# KMO_IO_MV1_0.net
KiCad netlist of a schematic drawn in EAGLE
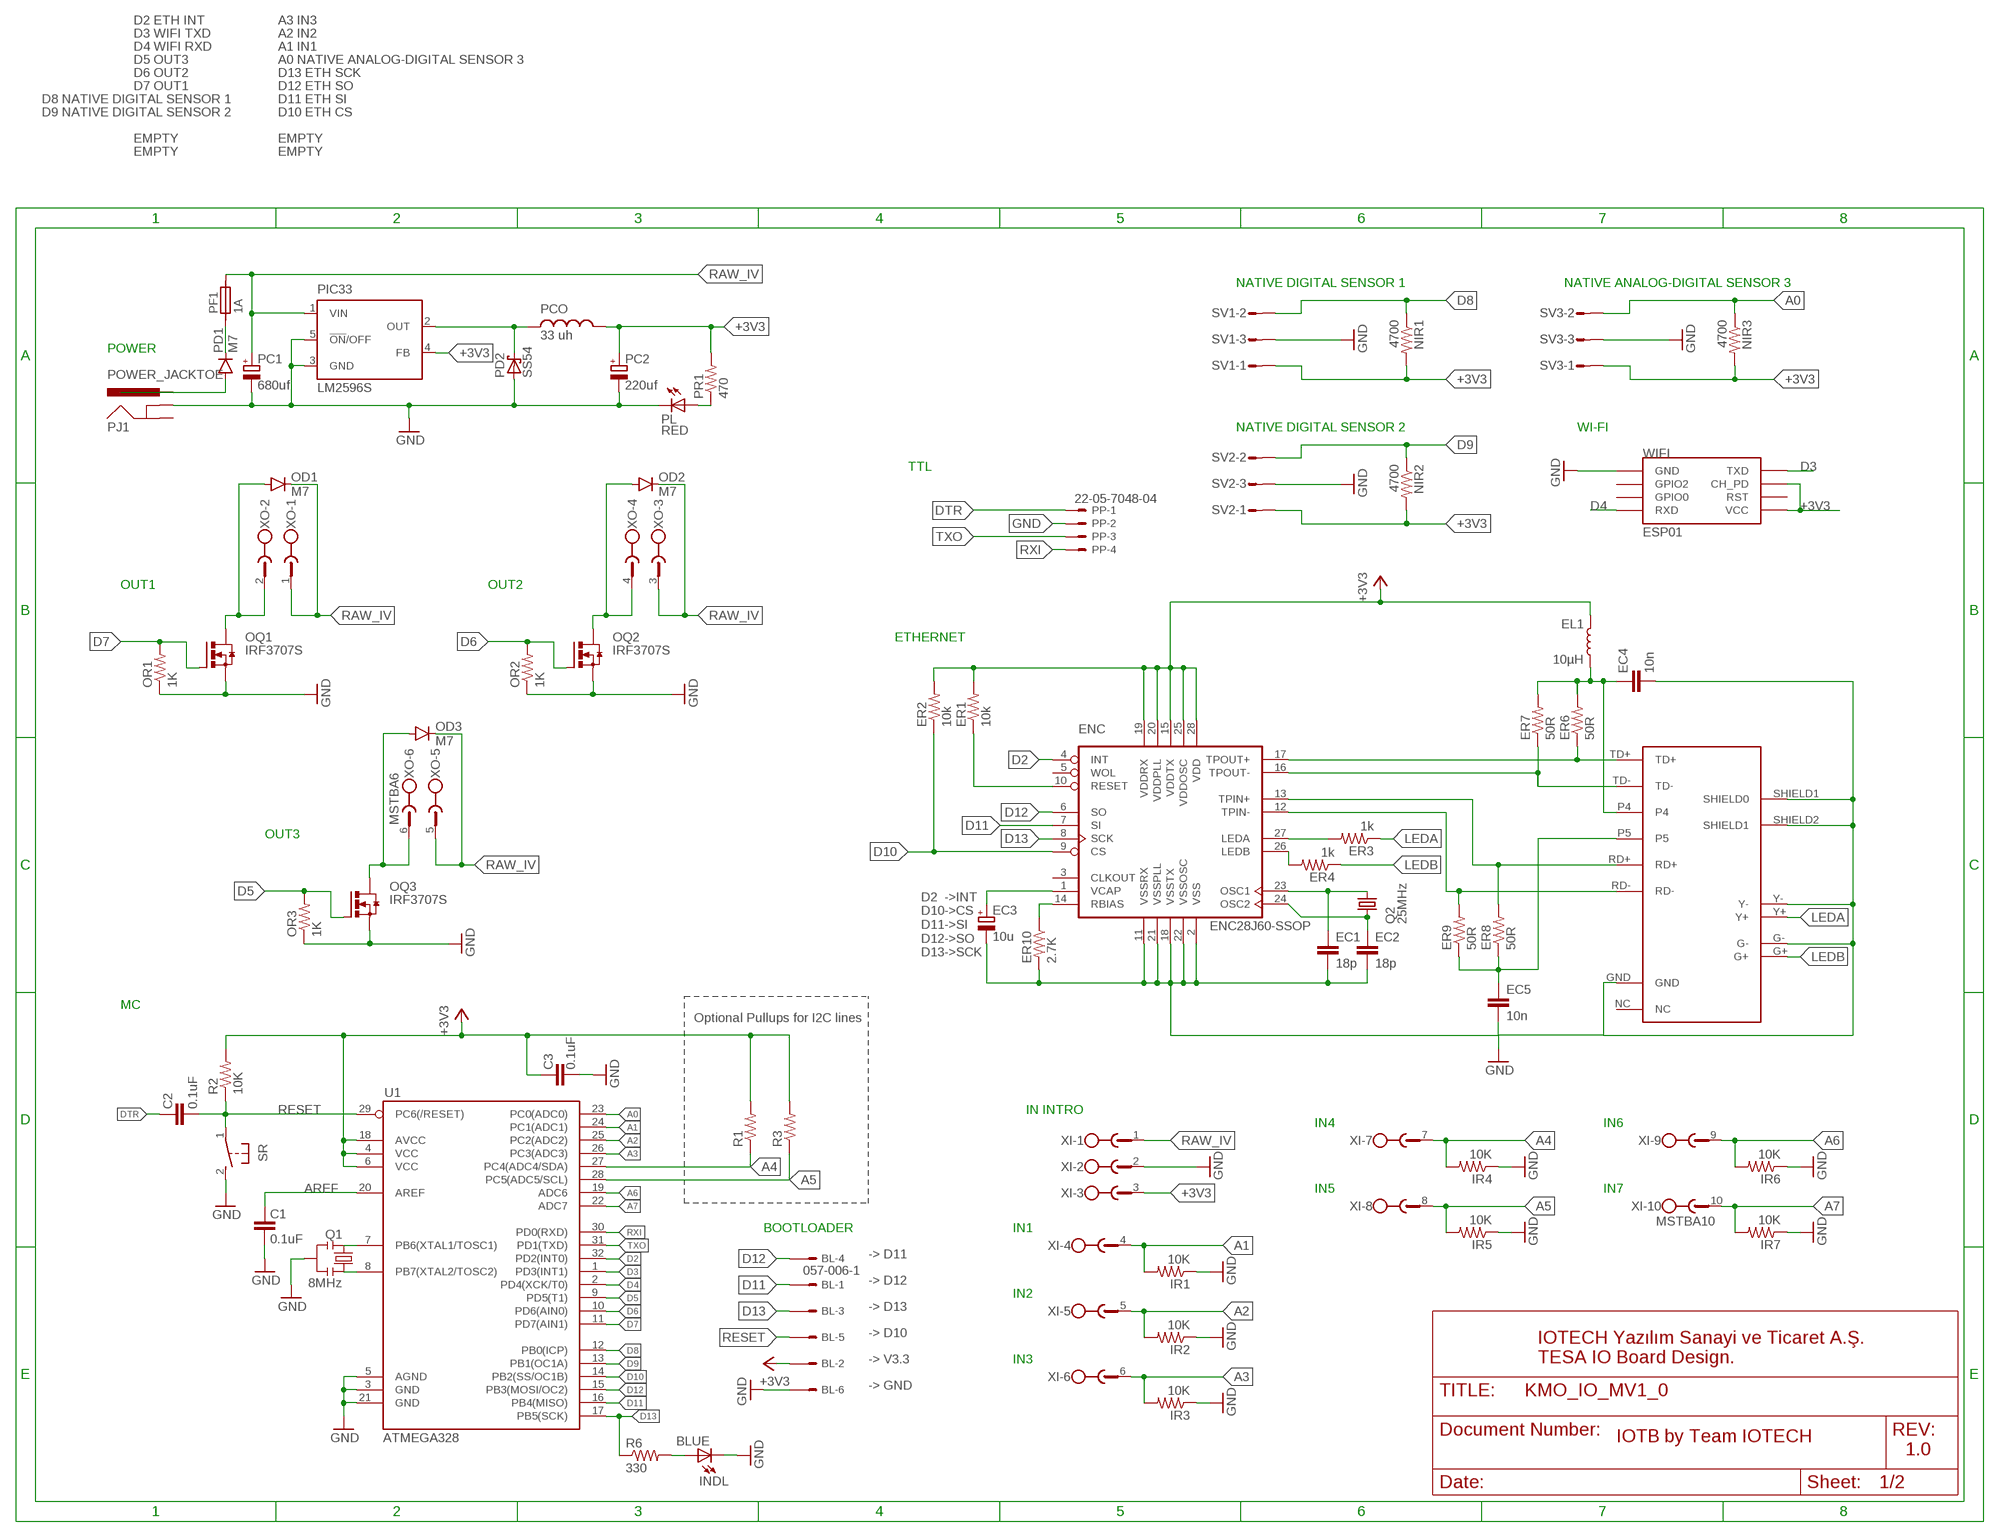
[diagram p0: schematic, sheet 1]
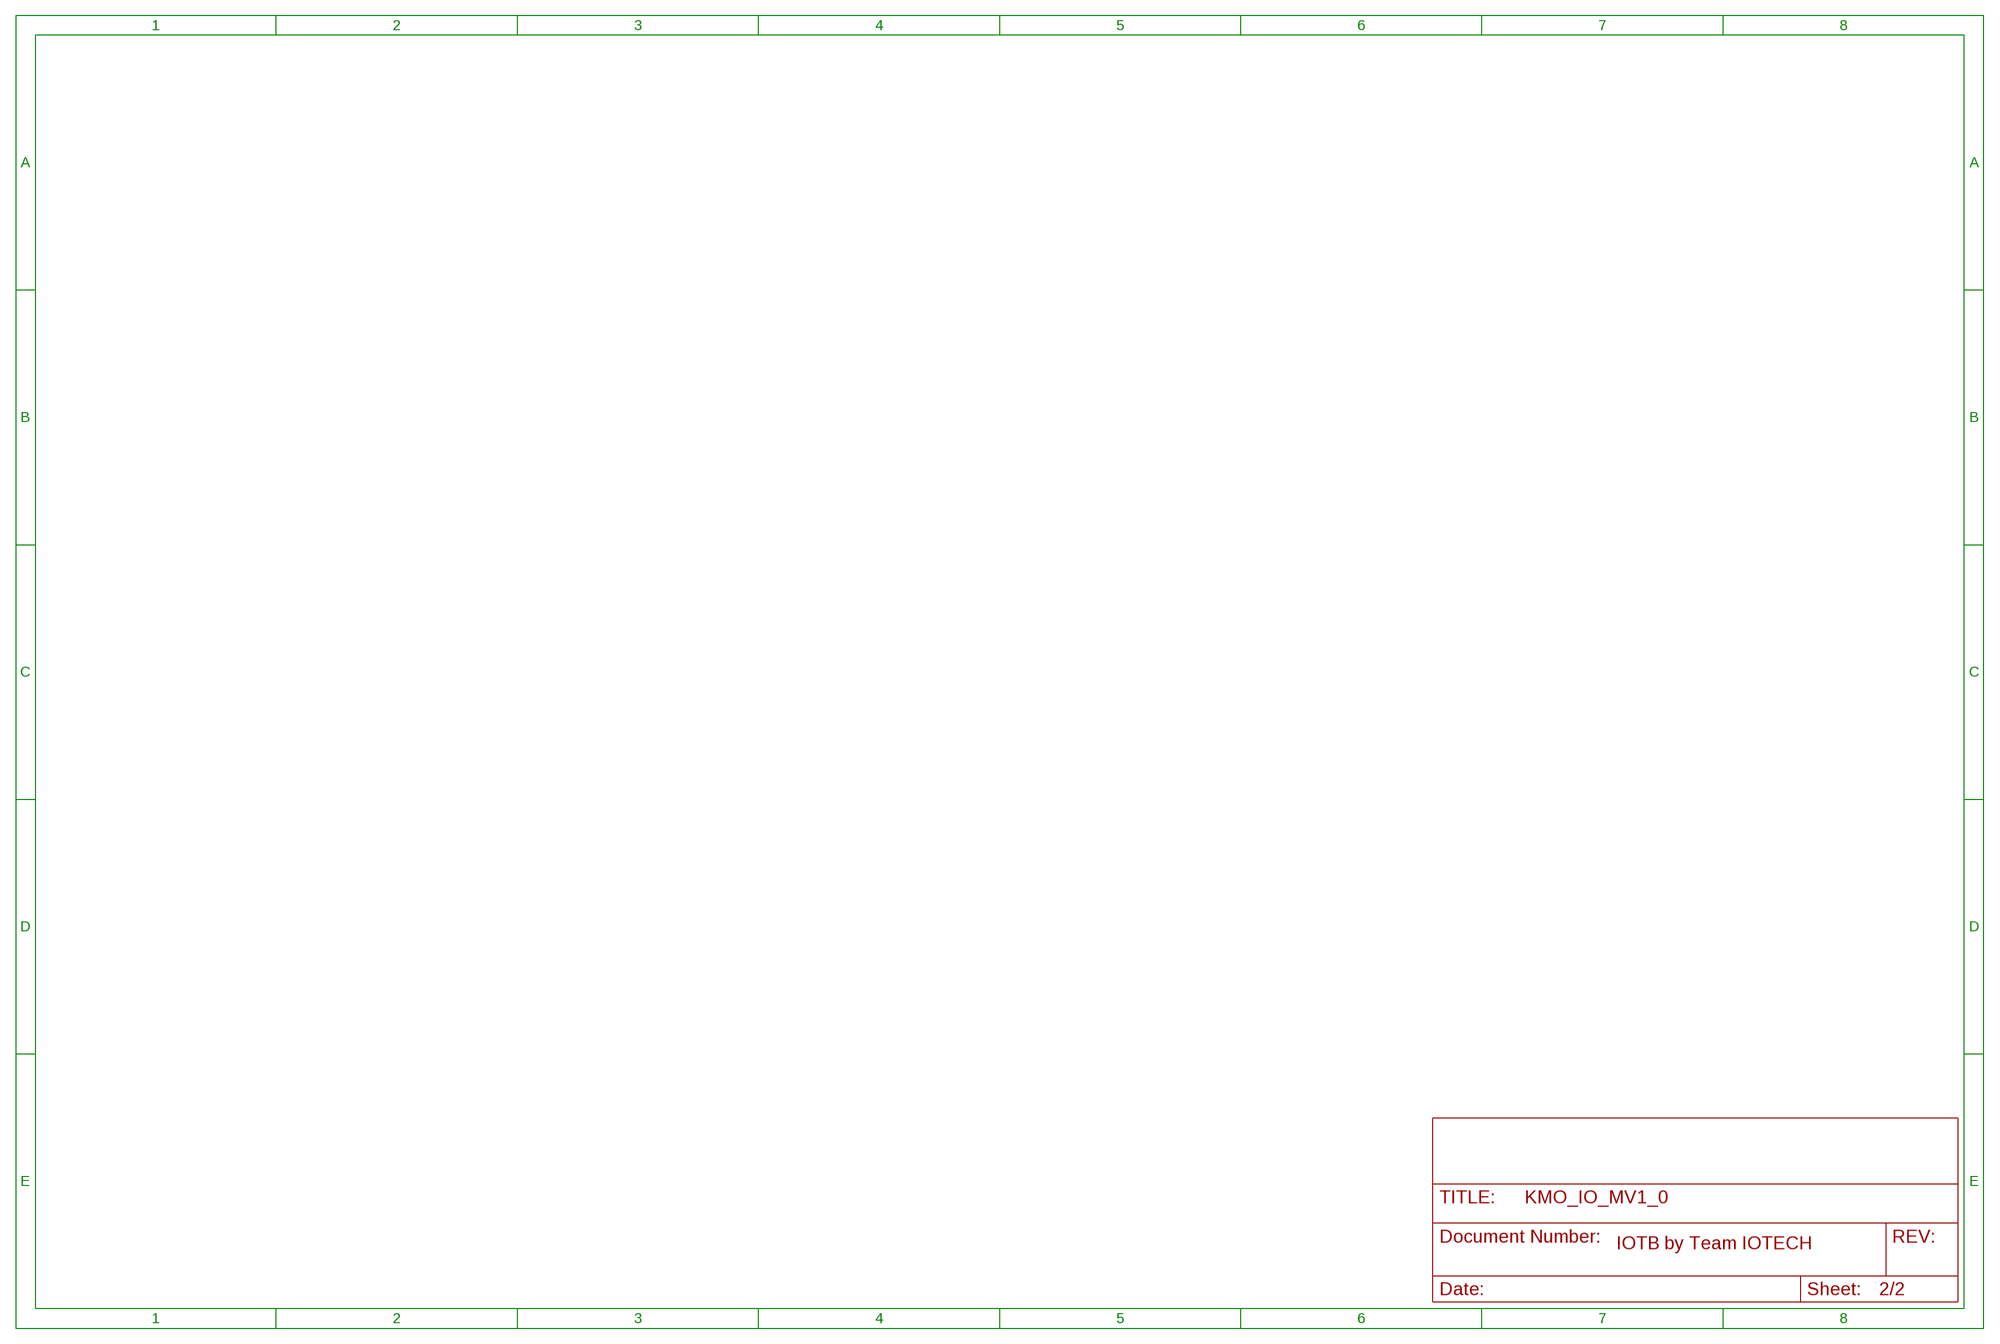
[diagram p1: schematic, sheet 2]

(export (version "E")
  (design (tool "Eeschema 10.0.6"))
  (components
    (comp (ref "BL")
      (value "057-006-1")
      (footprint "eagle-import:057-006-1")
      (libsource (lib "eagle-import") (part "057-006-1"))
    )
    (comp (ref "C1")
      (value "0.1uF")
      (footprint "eagle-import:0805")
      (libsource (lib "eagle-import") (part "CAP0805"))
    )
    (comp (ref "C2")
      (value "0.1uF")
      (footprint "eagle-import:0805")
      (libsource (lib "eagle-import") (part "CAP0805"))
    )
    (comp (ref "C3")
      (value "0.1uF")
      (footprint "eagle-import:0805")
      (libsource (lib "eagle-import") (part "CAP0805"))
    )
    (comp (ref "EC1")
      (value "18p")
      (footprint "eagle-import:0805")
      (libsource (lib "eagle-import") (part "CAP0805"))
    )
    (comp (ref "EC2")
      (value "18p")
      (footprint "eagle-import:0805")
      (libsource (lib "eagle-import") (part "CAP0805"))
    )
    (comp (ref "EC3")
      (value "10u")
      (footprint "eagle-import:CT3216")
      (libsource (lib "eagle-import") (part "CPOL-EUCT3216"))
    )
    (comp (ref "EC4")
      (value "10n")
      (footprint "eagle-import:0805")
      (libsource (lib "eagle-import") (part "CAP0805"))
    )
    (comp (ref "EC5")
      (value "10n")
      (footprint "eagle-import:0805")
      (libsource (lib "eagle-import") (part "CAP0805"))
    )
    (comp (ref "EL1")
      (value "10µH")
      (footprint "eagle-import:0805")
      (libsource (lib "eagle-import") (part "INDUCTOR-0805-3.3UH"))
    )
    (comp (ref "ENC")
      (value "ENC28J60-SSOP")
      (footprint "eagle-import:SSOP28")
      (libsource (lib "eagle-import") (part "ENC28J60-SSOP"))
    )
    (comp (ref "ER1")
      (value "10k")
      (footprint "eagle-import:0805")
      (libsource (lib "eagle-import") (part "RESISTOR0805-RES"))
    )
    (comp (ref "ER2")
      (value "10k")
      (footprint "eagle-import:0805")
      (libsource (lib "eagle-import") (part "RESISTOR0805-RES"))
    )
    (comp (ref "ER3")
      (value "1k")
      (footprint "eagle-import:0805")
      (libsource (lib "eagle-import") (part "RESISTOR0805-RES"))
    )
    (comp (ref "ER4")
      (value "1k")
      (footprint "eagle-import:0805")
      (libsource (lib "eagle-import") (part "RESISTOR0805-RES"))
    )
    (comp (ref "ER6")
      (value "50R")
      (footprint "eagle-import:0805")
      (libsource (lib "eagle-import") (part "RESISTOR0805-RES"))
    )
    (comp (ref "ER7")
      (value "50R")
      (footprint "eagle-import:0805")
      (libsource (lib "eagle-import") (part "RESISTOR0805-RES"))
    )
    (comp (ref "ER8")
      (value "50R")
      (footprint "eagle-import:0805")
      (libsource (lib "eagle-import") (part "RESISTOR0805-RES"))
    )
    (comp (ref "ER9")
      (value "50R")
      (footprint "eagle-import:0805")
      (libsource (lib "eagle-import") (part "RESISTOR0805-RES"))
    )
    (comp (ref "ER10")
      (value "2.7K")
      (footprint "eagle-import:0805")
      (libsource (lib "eagle-import") (part "RESISTOR0805-RES"))
    )
    (comp (ref "INDL")
      (value "BLUE")
      (footprint "eagle-import:CHIP-LED0805")
      (libsource (lib "eagle-import") (part "LEDCHIP-LED0805"))
    )
    (comp (ref "IR1")
      (value "10K")
      (footprint "eagle-import:0805")
      (libsource (lib "eagle-import") (part "RESISTOR0805-RES"))
    )
    (comp (ref "IR2")
      (value "10K")
      (footprint "eagle-import:0805")
      (libsource (lib "eagle-import") (part "RESISTOR0805-RES"))
    )
    (comp (ref "IR3")
      (value "10K")
      (footprint "eagle-import:0805")
      (libsource (lib "eagle-import") (part "RESISTOR0805-RES"))
    )
    (comp (ref "IR4")
      (value "10K")
      (footprint "eagle-import:0805")
      (libsource (lib "eagle-import") (part "RESISTOR0805-RES"))
    )
    (comp (ref "IR5")
      (value "10K")
      (footprint "eagle-import:0805")
      (libsource (lib "eagle-import") (part "RESISTOR0805-RES"))
    )
    (comp (ref "IR6")
      (value "10K")
      (footprint "eagle-import:0805")
      (libsource (lib "eagle-import") (part "RESISTOR0805-RES"))
    )
    (comp (ref "IR7")
      (value "10K")
      (footprint "eagle-import:0805")
      (libsource (lib "eagle-import") (part "RESISTOR0805-RES"))
    )
    (comp (ref "NIR1")
      (value "4700")
      (footprint "eagle-import:0805")
      (libsource (lib "eagle-import") (part "RESISTOR0805-RES"))
    )
    (comp (ref "NIR2")
      (value "4700")
      (footprint "eagle-import:0805")
      (libsource (lib "eagle-import") (part "RESISTOR0805-RES"))
    )
    (comp (ref "NIR3")
      (value "4700")
      (footprint "eagle-import:0805")
      (libsource (lib "eagle-import") (part "RESISTOR0805-RES"))
    )
    (comp (ref "OD1")
      (value "M7")
      (footprint "eagle-import:SMA-DIODE")
      (libsource (lib "eagle-import") (part "DIODESMA"))
    )
    (comp (ref "OD2")
      (value "M7")
      (footprint "eagle-import:SMA-DIODE")
      (libsource (lib "eagle-import") (part "DIODESMA"))
    )
    (comp (ref "OD3")
      (value "M7")
      (footprint "eagle-import:SMA-DIODE")
      (libsource (lib "eagle-import") (part "DIODESMA"))
    )
    (comp (ref "OQ1")
      (value "IRF3707S")
      (footprint "eagle-import:D2PACK")
      (libsource (lib "eagle-import") (part "IRF3704S"))
    )
    (comp (ref "OQ2")
      (value "IRF3707S")
      (footprint "eagle-import:D2PACK")
      (libsource (lib "eagle-import") (part "IRF3704S"))
    )
    (comp (ref "OQ3")
      (value "IRF3707S")
      (footprint "eagle-import:D2PACK")
      (libsource (lib "eagle-import") (part "IRF3704S"))
    )
    (comp (ref "OR1")
      (value "1K")
      (footprint "eagle-import:0805")
      (libsource (lib "eagle-import") (part "RESISTOR0805-RES"))
    )
    (comp (ref "OR2")
      (value "1K")
      (footprint "eagle-import:0805")
      (libsource (lib "eagle-import") (part "RESISTOR0805-RES"))
    )
    (comp (ref "OR3")
      (value "1K")
      (footprint "eagle-import:0805")
      (libsource (lib "eagle-import") (part "RESISTOR0805-RES"))
    )
    (comp (ref "PC1")
      (value "680uf")
      (footprint "eagle-import:140CLH-1010")
      (libsource (lib "eagle-import") (part "CPOL-EU140CLH-1010"))
    )
    (comp (ref "PC2")
      (value "220uf")
      (footprint "eagle-import:140CLH-1010")
      (libsource (lib "eagle-import") (part "CPOL-EU140CLH-1010"))
    )
    (comp (ref "PCO")
      (value "33 uh")
      (footprint "eagle-import:MSS1260")
      (libsource (lib "eagle-import") (part "MSS1260"))
    )
    (comp (ref "PD1")
      (value "M7")
      (footprint "eagle-import:SMA-DIODE")
      (libsource (lib "eagle-import") (part "DIODESMA"))
    )
    (comp (ref "PD2")
      (value "SS54")
      (footprint "eagle-import:SMB")
      (libsource (lib "eagle-import") (part "SCHOTTKY-DIODESMD"))
    )
    (comp (ref "PF1")
      (value "1A")
      (footprint "eagle-import:1820")
      (libsource (lib "eagle-import") (part "SIBA194600"))
    )
    (comp (ref "PIC33")
      (value "LM2596S")
      (footprint "eagle-import:TO263-5")
      (fields (field (name "MF") "NATIONAL SEMICONDUCTOR") (field (name "MPN") "LM2596S-ADJ/NOPB"))
      (libsource (lib "eagle-import") (part "LM2596S"))
    )
    (comp (ref "PJ1")
      (value "POWER_JACKTOE")
      (footprint "eagle-import:POWER_JACK_SMD_OVERPASTE_TOE")
      (libsource (lib "eagle-import") (part "POWER_JACKTOE"))
    )
    (comp (ref "PL")
      (value "RED")
      (footprint "eagle-import:CHIP-LED0805")
      (libsource (lib "eagle-import") (part "LEDCHIP-LED0805"))
    )
    (comp (ref "PP")
      (value "22-05-7048-04")
      (footprint "eagle-import:7395-04")
      (fields (field (name "MF") "MOLEX"))
      (libsource (lib "eagle-import") (part "22-?-0405-7048"))
    )
    (comp (ref "PR1")
      (value "470")
      (footprint "eagle-import:0805")
      (libsource (lib "eagle-import") (part "RESISTOR0805-RES"))
    )
    (comp (ref "Q1")
      (value "8MHz")
      (footprint "eagle-import:RESONATOR-SMD-1_1")
      (libsource (lib "eagle-import") (part "RESONATOR1{colon}1"))
    )
    (comp (ref "Q2")
      (value "25MHz")
      (footprint "eagle-import:5.0X3.2_2")
      (libsource (lib "eagle-import") (part "KX-9B"))
    )
    (comp (ref "R1")
      (value "RESISTOR0805-RES")
      (footprint "eagle-import:0805")
      (libsource (lib "eagle-import") (part "RESISTOR0805-RES"))
    )
    (comp (ref "R2")
      (value "10K")
      (footprint "eagle-import:0805")
      (libsource (lib "eagle-import") (part "RESISTOR0805-RES"))
    )
    (comp (ref "R3")
      (value "RESISTOR0805-RES")
      (footprint "eagle-import:0805")
      (libsource (lib "eagle-import") (part "RESISTOR0805-RES"))
    )
    (comp (ref "R6")
      (value "330")
      (footprint "eagle-import:0805")
      (libsource (lib "eagle-import") (part "RESISTOR0805-RES"))
    )
    (comp (ref "SR")
      (value "31-XX")
      (footprint "eagle-import:B3F-31XX")
      (fields (field (name "MPN") "B3F-3100"))
      (libsource (lib "eagle-import") (part "31-XX"))
    )
    (comp (ref "SV1")
      (value "S03P")
      (footprint "eagle-import:S03P")
      (libsource (lib "eagle-import") (part "S03P"))
    )
    (comp (ref "SV2")
      (value "S03P")
      (footprint "eagle-import:S03P")
      (libsource (lib "eagle-import") (part "S03P"))
    )
    (comp (ref "SV3")
      (value "S03P")
      (footprint "eagle-import:S03P")
      (libsource (lib "eagle-import") (part "S03P"))
    )
    (comp (ref "U$2")
      (value "HR911105A")
      (footprint "eagle-import:RJ45")
      (libsource (lib "eagle-import") (part "HR911105A"))
    )
    (comp (ref "U1")
      (value "ATMEGA328")
      (footprint "eagle-import:TQFP32-08")
      (libsource (lib "eagle-import") (part "ATMEGA168"))
    )
    (comp (ref "WIFI")
      (value "ESP01")
      (footprint "eagle-import:ESP01")
      (libsource (lib "eagle-import") (part "ESP01"))
    )
    (comp (ref "XI")
      (value "MSTBA10")
      (footprint "eagle-import:MSTBA10")
      (fields (field (name "MF") "FARNELL") (field (name "MPN") "1757323"))
      (libsource (lib "eagle-import") (part "MSTBA10"))
    )
    (comp (ref "XO")
      (value "MSTBA6")
      (footprint "eagle-import:MSTBA6")
      (fields (field (name "MF") "FARNELL") (field (name "MPN") "1757284"))
      (libsource (lib "eagle-import") (part "MSTBA6"))
    )
  )
  (nets
    (net (code "1") (name "+3V3") (class "Default")
      (node (ref "BL") (pin "2") (pinfunction "S_2") (pintype "passive"))
      (node (ref "C3") (pin "2") (pinfunction "2_2") (pintype "passive"))
      (node (ref "EL1") (pin "1") (pinfunction "1_1") (pintype "passive"))
      (node (ref "ENC") (pin "15") (pinfunction "VDDTX_15") (pintype "power_in"))
      (node (ref "ENC") (pin "19") (pinfunction "VDDRX_19") (pintype "power_in"))
      (node (ref "ENC") (pin "20") (pinfunction "VDDPLL_20") (pintype "power_in"))
      (node (ref "ENC") (pin "25") (pinfunction "VDDOSC_25") (pintype "power_in"))
      (node (ref "ENC") (pin "28") (pinfunction "VDD_28") (pintype "power_in"))
      (node (ref "ER1") (pin "2") (pinfunction "2_2") (pintype "passive"))
      (node (ref "ER2") (pin "2") (pinfunction "2_2") (pintype "passive"))
      (node (ref "NIR1") (pin "2") (pinfunction "2_2") (pintype "passive"))
      (node (ref "NIR2") (pin "2") (pinfunction "2_2") (pintype "passive"))
      (node (ref "NIR3") (pin "2") (pinfunction "2_2") (pintype "passive"))
      (node (ref "PC2") (pin "+") (pinfunction "+_+") (pintype "passive"))
      (node (ref "PCO") (pin "P$1") (pinfunction "P$1_P$1") (pintype "passive"))
      (node (ref "PIC33") (pin "4") (pinfunction "FB_4") (pintype "input"))
      (node (ref "PR1") (pin "2") (pinfunction "2_2") (pintype "passive"))
      (node (ref "R1") (pin "2") (pinfunction "2_2") (pintype "passive"))
      (node (ref "R2") (pin "2") (pinfunction "2_2") (pintype "passive"))
      (node (ref "R3") (pin "2") (pinfunction "2_2") (pintype "passive"))
      (node (ref "SV1") (pin "1") (pinfunction "S_1") (pintype "passive"))
      (node (ref "SV2") (pin "1") (pinfunction "S_1") (pintype "passive"))
      (node (ref "SV3") (pin "1") (pinfunction "S_1") (pintype "passive"))
      (node (ref "U1") (pin "18") (pinfunction "AVCC_18") (pintype "bidirectional"))
      (node (ref "U1") (pin "4") (pinfunction "VCC_4") (pintype "bidirectional"))
      (node (ref "U1") (pin "6") (pinfunction "VCC_6") (pintype "bidirectional"))
      (node (ref "WIFI") (pin "CH_PD") (pinfunction "CH_PD_CH_PD") (pintype "bidirectional"))
      (node (ref "WIFI") (pin "VCC") (pinfunction "VCC_VCC") (pintype "bidirectional"))
      (node (ref "XI") (pin "3") (pinfunction "1_3") (pintype "passive"))
    )
    (net (code "2") (name "A0") (class "Default")
      (node (ref "NIR3") (pin "1") (pinfunction "1_1") (pintype "passive"))
      (node (ref "SV3") (pin "2") (pinfunction "S_2") (pintype "passive"))
      (node (ref "U1") (pin "23") (pinfunction "PC0(ADC0)_23") (pintype "bidirectional"))
    )
    (net (code "3") (name "A1") (class "Default")
      (node (ref "IR1") (pin "2") (pinfunction "2_2") (pintype "passive"))
      (node (ref "U1") (pin "24") (pinfunction "PC1(ADC1)_24") (pintype "bidirectional"))
      (node (ref "XI") (pin "4") (pinfunction "1_4") (pintype "passive"))
    )
    (net (code "4") (name "A2") (class "Default")
      (node (ref "IR2") (pin "2") (pinfunction "2_2") (pintype "passive"))
      (node (ref "U1") (pin "25") (pinfunction "PC2(ADC2)_25") (pintype "bidirectional"))
      (node (ref "XI") (pin "5") (pinfunction "1_5") (pintype "passive"))
    )
    (net (code "5") (name "A3") (class "Default")
      (node (ref "IR3") (pin "2") (pinfunction "2_2") (pintype "passive"))
      (node (ref "U1") (pin "26") (pinfunction "PC3(ADC3)_26") (pintype "bidirectional"))
      (node (ref "XI") (pin "6") (pinfunction "1_6") (pintype "passive"))
    )
    (net (code "6") (name "A4") (class "Default")
      (node (ref "IR4") (pin "2") (pinfunction "2_2") (pintype "passive"))
      (node (ref "R1") (pin "1") (pinfunction "1_1") (pintype "passive"))
      (node (ref "U1") (pin "27") (pinfunction "PC4(ADC4/SDA)_27") (pintype "bidirectional"))
      (node (ref "XI") (pin "7") (pinfunction "1_7") (pintype "passive"))
    )
    (net (code "7") (name "A5") (class "Default")
      (node (ref "IR5") (pin "2") (pinfunction "2_2") (pintype "passive"))
      (node (ref "R3") (pin "1") (pinfunction "1_1") (pintype "passive"))
      (node (ref "U1") (pin "28") (pinfunction "PC5(ADC5/SCL)_28") (pintype "bidirectional"))
      (node (ref "XI") (pin "8") (pinfunction "1_8") (pintype "passive"))
    )
    (net (code "8") (name "A6") (class "Default")
      (node (ref "IR6") (pin "2") (pinfunction "2_2") (pintype "passive"))
      (node (ref "U1") (pin "19") (pinfunction "ADC6_19") (pintype "bidirectional"))
      (node (ref "XI") (pin "9") (pinfunction "1_9") (pintype "passive"))
    )
    (net (code "9") (name "A7") (class "Default")
      (node (ref "IR7") (pin "2") (pinfunction "2_2") (pintype "passive"))
      (node (ref "U1") (pin "22") (pinfunction "ADC7_22") (pintype "bidirectional"))
      (node (ref "XI") (pin "10") (pinfunction "1_10") (pintype "passive"))
    )
    (net (code "10") (name "AREF") (class "Default")
      (node (ref "C1") (pin "2") (pinfunction "2_2") (pintype "passive"))
      (node (ref "U1") (pin "20") (pinfunction "AREF_20") (pintype "bidirectional"))
    )
    (net (code "11") (name "D2") (class "Default")
      (node (ref "ENC") (pin "4") (pinfunction "INT_4") (pintype "output"))
      (node (ref "U1") (pin "32") (pinfunction "PD2(INT0)_32") (pintype "bidirectional"))
    )
    (net (code "12") (name "D3") (class "Default")
      (node (ref "U1") (pin "1") (pinfunction "PD3(INT1)_1") (pintype "bidirectional"))
      (node (ref "WIFI") (pin "TX") (pinfunction "TXD_TX") (pintype "bidirectional"))
    )
    (net (code "13") (name "D4") (class "Default")
      (node (ref "U1") (pin "2") (pinfunction "PD4(XCK/T0)_2") (pintype "bidirectional"))
      (node (ref "WIFI") (pin "RX") (pinfunction "RXD_RX") (pintype "bidirectional"))
    )
    (net (code "14") (name "D5") (class "Default")
      (node (ref "OQ3") (pin "1") (pinfunction "G_1") (pintype "passive"))
      (node (ref "OR3") (pin "2") (pinfunction "2_2") (pintype "passive"))
      (node (ref "U1") (pin "9") (pinfunction "PD5(T1)_9") (pintype "bidirectional"))
    )
    (net (code "15") (name "D6") (class "Default")
      (node (ref "OQ2") (pin "1") (pinfunction "G_1") (pintype "passive"))
      (node (ref "OR2") (pin "2") (pinfunction "2_2") (pintype "passive"))
      (node (ref "U1") (pin "10") (pinfunction "PD6(AIN0)_10") (pintype "bidirectional"))
    )
    (net (code "16") (name "D7") (class "Default")
      (node (ref "OQ1") (pin "1") (pinfunction "G_1") (pintype "passive"))
      (node (ref "OR1") (pin "2") (pinfunction "2_2") (pintype "passive"))
      (node (ref "U1") (pin "11") (pinfunction "PD7(AIN1)_11") (pintype "bidirectional"))
    )
    (net (code "17") (name "D8") (class "Default")
      (node (ref "NIR1") (pin "1") (pinfunction "1_1") (pintype "passive"))
      (node (ref "SV1") (pin "2") (pinfunction "S_2") (pintype "passive"))
      (node (ref "U1") (pin "12") (pinfunction "PB0(ICP)_12") (pintype "bidirectional"))
    )
    (net (code "18") (name "D9") (class "Default")
      (node (ref "NIR2") (pin "1") (pinfunction "1_1") (pintype "passive"))
      (node (ref "SV2") (pin "2") (pinfunction "S_2") (pintype "passive"))
      (node (ref "U1") (pin "13") (pinfunction "PB1(OC1A)_13") (pintype "bidirectional"))
    )
    (net (code "19") (name "D10") (class "Default")
      (node (ref "ENC") (pin "9") (pinfunction "CS_9") (pintype "input"))
      (node (ref "ER2") (pin "1") (pinfunction "1_1") (pintype "passive"))
      (node (ref "U1") (pin "14") (pinfunction "PB2(SS/OC1B)_14") (pintype "bidirectional"))
    )
    (net (code "20") (name "D11") (class "Default")
      (node (ref "BL") (pin "1") (pinfunction "S_1") (pintype "passive"))
      (node (ref "ENC") (pin "7") (pinfunction "SI_7") (pintype "input"))
      (node (ref "U1") (pin "16") (pinfunction "PB4(MISO)_16") (pintype "bidirectional"))
    )
    (net (code "21") (name "D12") (class "Default")
      (node (ref "BL") (pin "4") (pinfunction "S_4") (pintype "passive"))
      (node (ref "ENC") (pin "6") (pinfunction "SO_6") (pintype "output"))
      (node (ref "U1") (pin "15") (pinfunction "PB3(MOSI/OC2)_15") (pintype "bidirectional"))
    )
    (net (code "22") (name "D13") (class "Default")
      (node (ref "BL") (pin "3") (pinfunction "S_3") (pintype "passive"))
      (node (ref "ENC") (pin "8") (pinfunction "SCK_8") (pintype "input"))
      (node (ref "R6") (pin "1") (pinfunction "1_1") (pintype "passive"))
      (node (ref "U1") (pin "17") (pinfunction "PB5(SCK)_17") (pintype "bidirectional"))
    )
    (net (code "23") (name "DTR") (class "Default")
      (node (ref "C2") (pin "2") (pinfunction "2_2") (pintype "passive"))
      (node (ref "PP") (pin "1") (pinfunction "S_1") (pintype "passive"))
    )
    (net (code "24") (name "GND") (class "Default")
      (node (ref "BL") (pin "6") (pinfunction "S_6") (pintype "passive"))
      (node (ref "C1") (pin "1") (pinfunction "1_1") (pintype "passive"))
      (node (ref "C3") (pin "1") (pinfunction "1_1") (pintype "passive"))
      (node (ref "EC1") (pin "2") (pinfunction "2_2") (pintype "passive"))
      (node (ref "EC2") (pin "2") (pinfunction "2_2") (pintype "passive"))
      (node (ref "EC3") (pin "-") (pinfunction "-_-") (pintype "passive"))
      (node (ref "EC4") (pin "2") (pinfunction "2_2") (pintype "passive"))
      (node (ref "EC5") (pin "2") (pinfunction "2_2") (pintype "passive"))
      (node (ref "ENC") (pin "11") (pinfunction "VSSRX_11") (pintype "power_in"))
      (node (ref "ENC") (pin "18") (pinfunction "VSSTX_18") (pintype "power_in"))
      (node (ref "ENC") (pin "2") (pinfunction "VSS_2") (pintype "power_in"))
      (node (ref "ENC") (pin "21") (pinfunction "VSSPLL_21") (pintype "power_in"))
      (node (ref "ENC") (pin "22") (pinfunction "VSSOSC_22") (pintype "power_in"))
      (node (ref "ER10") (pin "2") (pinfunction "2_2") (pintype "passive"))
      (node (ref "INDL") (pin "C") (pinfunction "C_C") (pintype "passive"))
      (node (ref "IR1") (pin "1") (pinfunction "1_1") (pintype "passive"))
      (node (ref "IR2") (pin "1") (pinfunction "1_1") (pintype "passive"))
      (node (ref "IR3") (pin "1") (pinfunction "1_1") (pintype "passive"))
      (node (ref "IR4") (pin "1") (pinfunction "1_1") (pintype "passive"))
      (node (ref "IR5") (pin "1") (pinfunction "1_1") (pintype "passive"))
      (node (ref "IR6") (pin "1") (pinfunction "1_1") (pintype "passive"))
      (node (ref "IR7") (pin "1") (pinfunction "1_1") (pintype "passive"))
      (node (ref "OQ1") (pin "3") (pinfunction "S_3") (pintype "passive"))
      (node (ref "OQ2") (pin "3") (pinfunction "S_3") (pintype "passive"))
      (node (ref "OQ3") (pin "3") (pinfunction "S_3") (pintype "passive"))
      (node (ref "OR1") (pin "1") (pinfunction "1_1") (pintype "passive"))
      (node (ref "OR2") (pin "1") (pinfunction "1_1") (pintype "passive"))
      (node (ref "OR3") (pin "1") (pinfunction "1_1") (pintype "passive"))
      (node (ref "PC1") (pin "-") (pinfunction "-_-") (pintype "passive"))
      (node (ref "PC2") (pin "-") (pinfunction "-_-") (pintype "passive"))
      (node (ref "PD2") (pin "A") (pinfunction "A_A") (pintype "passive"))
      (node (ref "PIC33") (pin "3") (pinfunction "GND_3") (pintype "power_in"))
      (node (ref "PIC33") (pin "5") (pinfunction "~{ON}/OFF_5") (pintype "input"))
      (node (ref "PJ1") (pin "GND") (pinfunction "GNDBREAK_GND") (pintype "bidirectional"))
      (node (ref "PL") (pin "C") (pinfunction "C_C") (pintype "passive"))
      (node (ref "PP") (pin "2") (pinfunction "S_2") (pintype "passive"))
      (node (ref "Q1") (pin "2") (pinfunction "2_2") (pintype "passive"))
      (node (ref "SR") (pin "2") (pinfunction "S_2") (pintype "passive"))
      (node (ref "SV1") (pin "3") (pinfunction "S_3") (pintype "passive"))
      (node (ref "SV2") (pin "3") (pinfunction "S_3") (pintype "passive"))
      (node (ref "SV3") (pin "3") (pinfunction "S_3") (pintype "passive"))
      (node (ref "U$2") (pin "G-") (pinfunction "G-_G-") (pintype "bidirectional"))
      (node (ref "U$2") (pin "GND") (pinfunction "GND_GND") (pintype "bidirectional"))
      (node (ref "U$2") (pin "SHIELD1") (pinfunction "SHIELD0_SHIELD1") (pintype "bidirectional"))
      (node (ref "U$2") (pin "SHIELD2") (pinfunction "SHIELD1_SHIELD2") (pintype "bidirectional"))
      (node (ref "U$2") (pin "Y-") (pinfunction "Y-_Y-") (pintype "bidirectional"))
      (node (ref "U1") (pin "21") (pinfunction "GND_21") (pintype "bidirectional"))
      (node (ref "U1") (pin "3") (pinfunction "GND_3") (pintype "bidirectional"))
      (node (ref "U1") (pin "5") (pinfunction "AGND_5") (pintype "bidirectional"))
      (node (ref "WIFI") (pin "GND") (pinfunction "GND_GND") (pintype "bidirectional"))
      (node (ref "XI") (pin "2") (pinfunction "1_2") (pintype "passive"))
    )
    (net (code "25") (name "LEDA") (class "Default")
      (node (ref "ER3") (pin "1") (pinfunction "1_1") (pintype "passive"))
      (node (ref "U$2") (pin "Y+") (pinfunction "Y+_Y+") (pintype "bidirectional"))
    )
    (net (code "26") (name "LEDB") (class "Default")
      (node (ref "ER4") (pin "1") (pinfunction "1_1") (pintype "passive"))
      (node (ref "U$2") (pin "G+") (pinfunction "G+_G+") (pintype "bidirectional"))
    )
    (net (code "27") (name "Net-(EC4-Pad1)") (class "Default")
      (node (ref "EC4") (pin "1") (pinfunction "1_1") (pintype "passive"))
      (node (ref "EL1") (pin "2") (pinfunction "2_2") (pintype "passive"))
      (node (ref "ER6") (pin "2") (pinfunction "2_2") (pintype "passive"))
      (node (ref "ER7") (pin "2") (pinfunction "2_2") (pintype "passive"))
      (node (ref "U$2") (pin "P4") (pinfunction "P4_P4") (pintype "bidirectional"))
    )
    (net (code "28") (name "Net-(EC5-Pad1)") (class "Default")
      (node (ref "EC5") (pin "1") (pinfunction "1_1") (pintype "passive"))
      (node (ref "ER8") (pin "1") (pinfunction "1_1") (pintype "passive"))
      (node (ref "ER9") (pin "1") (pinfunction "1_1") (pintype "passive"))
      (node (ref "U$2") (pin "P5") (pinfunction "P5_P5") (pintype "bidirectional"))
    )
    (net (code "29") (name "Net-(ENC-LEDA)") (class "Default")
      (node (ref "ENC") (pin "27") (pinfunction "LEDA_27") (pintype "output"))
      (node (ref "ER3") (pin "2") (pinfunction "2_2") (pintype "passive"))
    )
    (net (code "30") (name "Net-(ENC-LEDB)") (class "Default")
      (node (ref "ENC") (pin "26") (pinfunction "LEDB_26") (pintype "output"))
      (node (ref "ER4") (pin "2") (pinfunction "2_2") (pintype "passive"))
    )
    (net (code "31") (name "Net-(ENC-OSC1)") (class "Default")
      (node (ref "EC1") (pin "1") (pinfunction "1_1") (pintype "passive"))
      (node (ref "ENC") (pin "23") (pinfunction "OSC1_23") (pintype "input"))
      (node (ref "Q2") (pin "2") (pinfunction "2_2") (pintype "passive"))
    )
    (net (code "32") (name "Net-(ENC-OSC2)") (class "Default")
      (node (ref "EC2") (pin "1") (pinfunction "1_1") (pintype "passive"))
      (node (ref "ENC") (pin "24") (pinfunction "OSC2_24") (pintype "output"))
      (node (ref "Q2") (pin "1") (pinfunction "1_1") (pintype "passive"))
    )
    (net (code "33") (name "Net-(ENC-RBIAS)") (class "Default")
      (node (ref "ENC") (pin "14") (pinfunction "RBIAS_14") (pintype "passive"))
      (node (ref "ER10") (pin "1") (pinfunction "1_1") (pintype "passive"))
    )
    (net (code "34") (name "Net-(ENC-RESET)") (class "Default")
      (node (ref "ENC") (pin "10") (pinfunction "RESET_10") (pintype "input"))
      (node (ref "ER1") (pin "1") (pinfunction "1_1") (pintype "passive"))
    )
    (net (code "35") (name "Net-(ENC-TPIN+)") (class "Default")
      (node (ref "ENC") (pin "13") (pinfunction "TPIN+_13") (pintype "input"))
      (node (ref "ER8") (pin "2") (pinfunction "2_2") (pintype "passive"))
      (node (ref "U$2") (pin "RD+") (pinfunction "RD+_RD+") (pintype "bidirectional"))
    )
    (net (code "36") (name "Net-(ENC-TPIN-)") (class "Default")
      (node (ref "ENC") (pin "12") (pinfunction "TPIN-_12") (pintype "input"))
      (node (ref "ER9") (pin "2") (pinfunction "2_2") (pintype "passive"))
      (node (ref "U$2") (pin "RD-") (pinfunction "RD-_RD-") (pintype "bidirectional"))
    )
    (net (code "37") (name "Net-(ENC-TPOUT+)") (class "Default")
      (node (ref "ENC") (pin "17") (pinfunction "TPOUT+_17") (pintype "output"))
      (node (ref "ER6") (pin "1") (pinfunction "1_1") (pintype "passive"))
      (node (ref "U$2") (pin "TD+") (pinfunction "TD+_TD+") (pintype "bidirectional"))
    )
    (net (code "38") (name "Net-(ENC-TPOUT-)") (class "Default")
      (node (ref "ENC") (pin "16") (pinfunction "TPOUT-_16") (pintype "output"))
      (node (ref "ER7") (pin "1") (pinfunction "1_1") (pintype "passive"))
      (node (ref "U$2") (pin "TD-") (pinfunction "TD-_TD-") (pintype "bidirectional"))
    )
    (net (code "39") (name "Net-(ENC-VCAP)") (class "Default")
      (node (ref "EC3") (pin "+") (pinfunction "+_+") (pintype "passive"))
      (node (ref "ENC") (pin "1") (pinfunction "VCAP_1") (pintype "power_in"))
    )
    (net (code "40") (name "Net-(INDL-PadA)") (class "Default")
      (node (ref "INDL") (pin "A") (pinfunction "A_A") (pintype "passive"))
      (node (ref "R6") (pin "2") (pinfunction "2_2") (pintype "passive"))
    )
    (net (code "41") (name "Net-(OQ1-D)") (class "Default")
      (node (ref "OD1") (pin "A") (pinfunction "A_A") (pintype "passive"))
      (node (ref "OQ1") (pin "2") (pinfunction "D_2") (pintype "passive"))
      (node (ref "XO") (pin "2") (pinfunction "1_2") (pintype "passive"))
    )
    (net (code "42") (name "Net-(OQ2-D)") (class "Default")
      (node (ref "OD2") (pin "A") (pinfunction "A_A") (pintype "passive"))
      (node (ref "OQ2") (pin "2") (pinfunction "D_2") (pintype "passive"))
      (node (ref "XO") (pin "4") (pinfunction "1_4") (pintype "passive"))
    )
    (net (code "43") (name "Net-(OQ3-D)") (class "Default")
      (node (ref "OD3") (pin "A") (pinfunction "A_A") (pintype "passive"))
      (node (ref "OQ3") (pin "2") (pinfunction "D_2") (pintype "passive"))
      (node (ref "XO") (pin "6") (pinfunction "1_6") (pintype "passive"))
    )
    (net (code "44") (name "Net-(PD1-PadC)") (class "Default")
      (node (ref "PD1") (pin "C") (pinfunction "C_C") (pintype "passive"))
      (node (ref "PF1") (pin "1") (pinfunction "1_1") (pintype "passive"))
    )
    (net (code "45") (name "Net-(PIC33-OUT)") (class "Default")
      (node (ref "PCO") (pin "P$2") (pinfunction "P$2_P$2") (pintype "passive"))
      (node (ref "PD2") (pin "C") (pinfunction "C_C") (pintype "passive"))
      (node (ref "PIC33") (pin "2") (pinfunction "OUT_2") (pintype "output"))
    )
    (net (code "46") (name "Net-(PJ1-PWR)") (class "Default")
      (node (ref "PD1") (pin "A") (pinfunction "A_A") (pintype "passive"))
      (node (ref "PJ1") (pin "VIN0") (pinfunction "PWR_VIN0") (pintype "bidirectional"))
    )
    (net (code "47") (name "Net-(PL-PadA)") (class "Default")
      (node (ref "PL") (pin "A") (pinfunction "A_A") (pintype "passive"))
      (node (ref "PR1") (pin "1") (pinfunction "1_1") (pintype "passive"))
    )
    (net (code "48") (name "Net-(U1-PB6(XTAL1{slash}TOSC1))") (class "Default")
      (node (ref "Q1") (pin "1") (pinfunction "1_1") (pintype "passive"))
      (node (ref "U1") (pin "7") (pinfunction "PB6(XTAL1/TOSC1)_7") (pintype "bidirectional"))
    )
    (net (code "49") (name "Net-(U1-PB7(XTAL2{slash}TOSC2))") (class "Default")
      (node (ref "Q1") (pin "3") (pinfunction "3_3") (pintype "passive"))
      (node (ref "U1") (pin "8") (pinfunction "PB7(XTAL2/TOSC2)_8") (pintype "bidirectional"))
    )
    (net (code "50") (name "RAW_IV") (class "Default")
      (node (ref "OD1") (pin "C") (pinfunction "C_C") (pintype "passive"))
      (node (ref "OD2") (pin "C") (pinfunction "C_C") (pintype "passive"))
      (node (ref "OD3") (pin "C") (pinfunction "C_C") (pintype "passive"))
      (node (ref "PC1") (pin "+") (pinfunction "+_+") (pintype "passive"))
      (node (ref "PF1") (pin "2") (pinfunction "2_2") (pintype "passive"))
      (node (ref "PIC33") (pin "1") (pinfunction "VIN_1") (pintype "input"))
      (node (ref "XI") (pin "1") (pinfunction "1_1") (pintype "passive"))
      (node (ref "XO") (pin "1") (pinfunction "1_1") (pintype "passive"))
      (node (ref "XO") (pin "3") (pinfunction "1_3") (pintype "passive"))
      (node (ref "XO") (pin "5") (pinfunction "1_5") (pintype "passive"))
    )
    (net (code "51") (name "RESET") (class "Default")
      (node (ref "BL") (pin "5") (pinfunction "S_5") (pintype "passive"))
      (node (ref "C2") (pin "1") (pinfunction "1_1") (pintype "passive"))
      (node (ref "R2") (pin "1") (pinfunction "1_1") (pintype "passive"))
      (node (ref "SR") (pin "1") (pinfunction "P_1") (pintype "passive"))
      (node (ref "U1") (pin "29") (pinfunction "PC6(/RESET)_29") (pintype "bidirectional"))
    )
    (net (code "52") (name "RXI") (class "Default")
      (node (ref "PP") (pin "4") (pinfunction "S_4") (pintype "passive"))
      (node (ref "U1") (pin "30") (pinfunction "PD0(RXD)_30") (pintype "bidirectional"))
    )
    (net (code "53") (name "TXO") (class "Default")
      (node (ref "PP") (pin "3") (pinfunction "S_3") (pintype "passive"))
      (node (ref "U1") (pin "31") (pinfunction "PD1(TXD)_31") (pintype "bidirectional"))
    )
    (net (code "54") (name "unconnected-(ENC-CLKOUT-Pad3)") (class "Default")
      (node (ref "ENC") (pin "3") (pinfunction "CLKOUT_3") (pintype "output"))
    )
    (net (code "55") (name "unconnected-(ENC-WOL-Pad5)") (class "Default")
      (node (ref "ENC") (pin "5") (pinfunction "WOL_5") (pintype "output"))
    )
    (net (code "56") (name "unconnected-(PJ1-GND-PadP$4)") (class "Default")
      (node (ref "PJ1") (pin "P$4") (pinfunction "GND_P$4") (pintype "bidirectional"))
    )
    (net (code "57") (name "unconnected-(U$2-PadNC)") (class "Default")
      (node (ref "U$2") (pin "NC") (pinfunction "NC_NC") (pintype "bidirectional"))
    )
    (net (code "58") (name "unconnected-(WIFI-PadGPIO0)") (class "Default")
      (node (ref "WIFI") (pin "GPIO0") (pinfunction "GPIO0_GPIO0") (pintype "bidirectional"))
    )
    (net (code "59") (name "unconnected-(WIFI-PadGPIO2)") (class "Default")
      (node (ref "WIFI") (pin "GPIO2") (pinfunction "GPIO2_GPIO2") (pintype "bidirectional"))
    )
    (net (code "60") (name "unconnected-(WIFI-PadRST)") (class "Default")
      (node (ref "WIFI") (pin "RST") (pinfunction "RST_RST") (pintype "bidirectional"))
    )
  )
)
